# Sheet2.net
KiCad netlist of a schematic drawn in Altium Designer
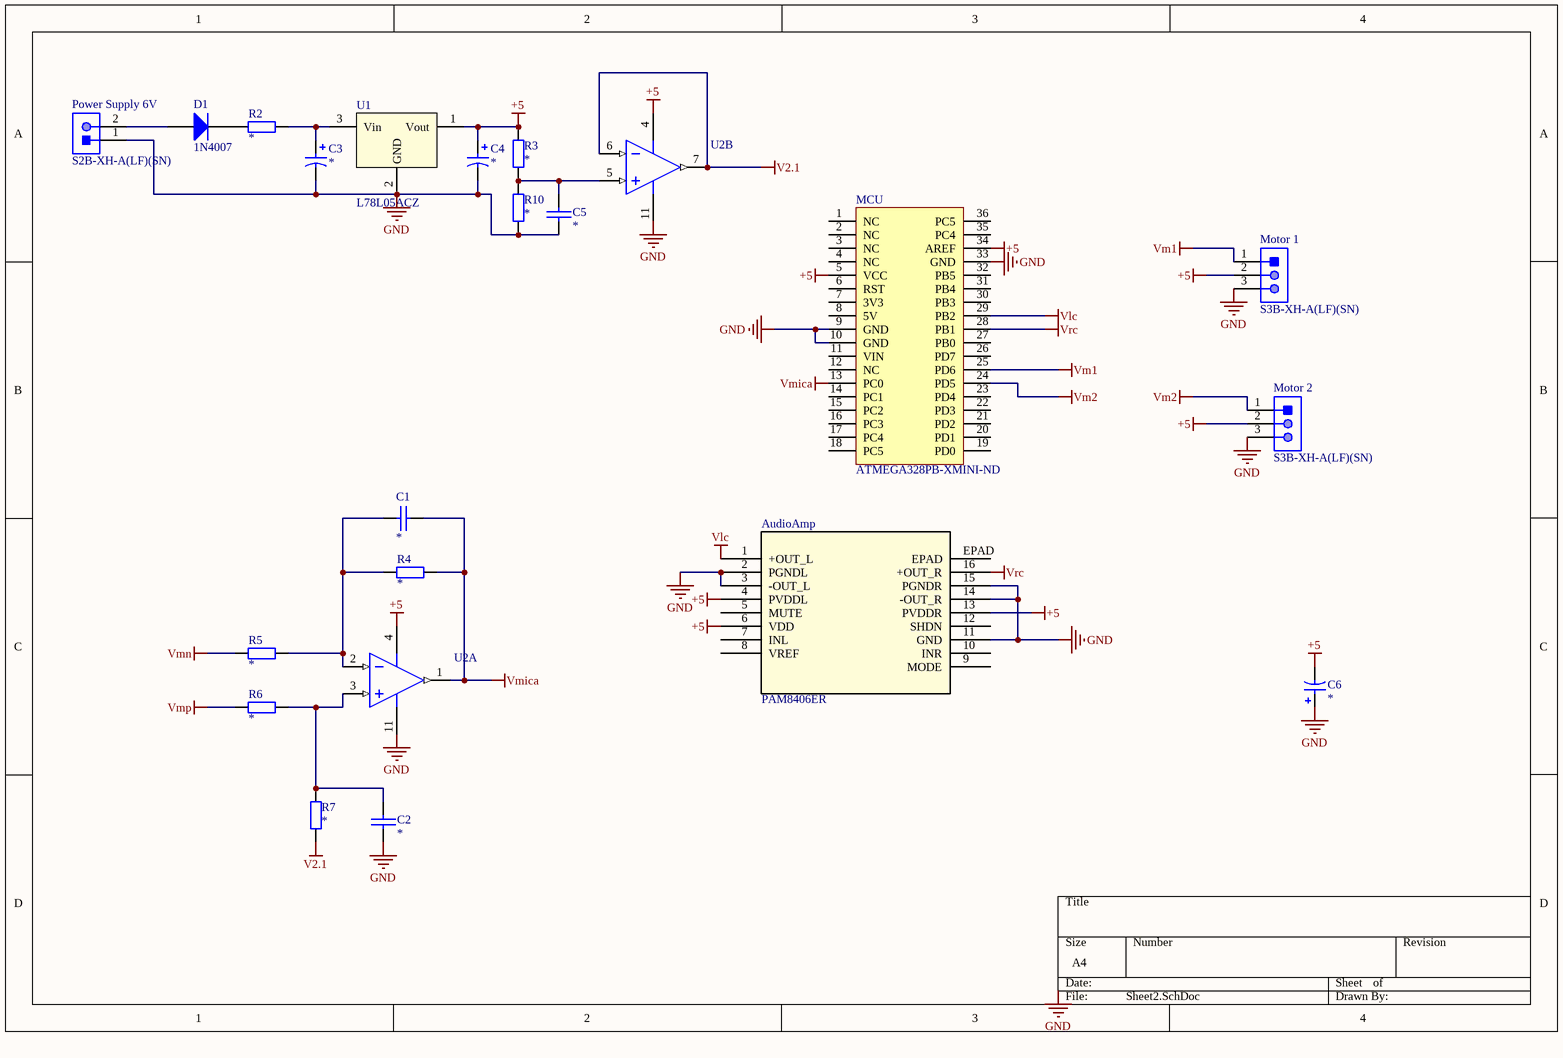
[diagram p0: Sheet2.SchDoc]

(export (version "E")
  (design (tool "Eeschema 10.0.6"))
  (components
    (comp (ref "AudioAmp")
      (value "PAM8406ER")
      (footprint "PAM8406ER_DIO")
      (description "Description")
      (fields (field (name "COPYRIGHT") "Copyright (C) 2025 Ultra Librarian. All rights reserved."))
      (libsource (lib "PAM8406ER") (part "PAM8406ER"))
    )
    (comp (ref "C1")
      (value "*")
      (footprint "CCAP-5P0")
      (description "TH ceramic capacitor with 5mm pitch")
      (libsource (lib "EE209_Library") (part "CerCap_TH_5P0"))
    )
    (comp (ref "C2")
      (value "*")
      (footprint "CCAP-5P0")
      (description "TH ceramic capacitor with 5mm pitch")
      (libsource (lib "EE209_Library") (part "CerCap_TH_5P0"))
    )
    (comp (ref "C3")
      (value "*")
      (footprint "CAP-RAD-2.5mm Pitch")
      (description "Electrolytic capacitor with radial package, 2mm pitch and 5.2mm diameter")
      (fields (field (name "PUBLISHER") "Altium Limited"))
      (libsource (lib "EE209_Library") (part "ElecCap_TH_2P0"))
    )
    (comp (ref "C4")
      (value "*")
      (footprint "CAP-RAD-2.5mm Pitch")
      (description "Electrolytic capacitor with radial package, 2mm pitch and 5.2mm diameter")
      (fields (field (name "PUBLISHER") "Altium Limited"))
      (libsource (lib "EE209_Library") (part "ElecCap_TH_2P0"))
    )
    (comp (ref "C5")
      (value "*")
      (footprint "CCAP-5P0")
      (description "TH ceramic capacitor with 5mm pitch")
      (libsource (lib "EE209_Library") (part "CerCap_TH_5P0"))
    )
    (comp (ref "C6")
      (value "*")
      (footprint "CAP-RAD-2.5mm Pitch")
      (description "Electrolytic capacitor with radial package, 2mm pitch and 5.2mm diameter")
      (fields (field (name "PUBLISHER") "Altium Limited"))
      (libsource (lib "EE209_Library") (part "ElecCap_TH_2P0"))
    )
    (comp (ref "D1")
      (value "1N4007")
      (footprint "1N4007-MFG")
      (description "1N4007 1000V standard axial diode")
      (libsource (lib "EE209_Library") (part "1N4007_TH_4AX0"))
    )
    (comp (ref "MCU")
      (value "ATmega328PB Xplained Mini Header")
      (footprint "ATmeg328P Xplained")
      (description "Dual 18-pin headers connecting to ATmega328PB Xplained Mini")
      (fields
        (field (name "MANUFACTURER") "Microchip Technology")
        (field (name "MANUFACTURER PART NUMBER") "ATMEGA328PB-XMINI")
        (field (name "SUPPLIER PART NUMBER 1") "ATMEGA328PB-XMINI-ND")
      )
      (libsource (lib "EE209_Library") (part "ATmega328PBXplained_TH"))
    )
    (comp (ref "Motor 1")
      (value "S3B-XH-A(LF)(SN)")
      (footprint "JST-S3B-XH-A(LF)(SN)_V")
      (fields (field (name "MANUFACTURER") "JST"))
      (libsource (lib "Elia Stolk") (part "CN-1P-M-R3"))
    )
    (comp (ref "Motor 2")
      (value "S3B-XH-A(LF)(SN)")
      (footprint "JST-S3B-XH-A(LF)(SN)_V")
      (fields (field (name "MANUFACTURER") "JST"))
      (libsource (lib "Elia Stolk") (part "CN-1P-M-R3"))
    )
    (comp (ref "Power Supply 6V")
      (value "S2B-XH-A(LF)(SN)")
      (footprint "JST-S2B-XH-A(LF)(SN)_V")
      (fields (field (name "MANUFACTURER") "JST"))
      (libsource (lib "Elia Stolk") (part "CN-1P-M-R2"))
    )
    (comp (ref "R2")
      (value "*")
      (footprint "AXIAL-0.4")
      (description "Through hole resistor")
      (fields (field (name "PUBLISHER") "Altium Limited"))
      (libsource (lib "EE209_Library") (part "Res_TH_0AX4"))
    )
    (comp (ref "R3")
      (value "*")
      (footprint "AXIAL-0.4")
      (description "Through hole resistor")
      (fields (field (name "PUBLISHER") "Altium Limited"))
      (libsource (lib "") (part "Res_TH_0AX4_2"))
    )
    (comp (ref "R4")
      (value "*")
      (footprint "AXIAL-0.4")
      (description "Through hole resistor")
      (fields (field (name "PUBLISHER") "Altium Limited"))
      (libsource (lib "EE209_Library") (part "Res_TH_0AX4"))
    )
    (comp (ref "R5")
      (value "*")
      (footprint "AXIAL-0.4")
      (description "Through hole resistor")
      (fields (field (name "PUBLISHER") "Altium Limited"))
      (libsource (lib "") (part "Res_TH_0AX4_1"))
    )
    (comp (ref "R6")
      (value "*")
      (footprint "AXIAL-0.4")
      (description "Through hole resistor")
      (fields (field (name "PUBLISHER") "Altium Limited"))
      (libsource (lib "") (part "Res_TH_0AX4_1"))
    )
    (comp (ref "R7")
      (value "*")
      (footprint "AXIAL-0.4")
      (description "Through hole resistor")
      (fields (field (name "PUBLISHER") "Altium Limited"))
      (libsource (lib "") (part "Res_TH_0AX4_2"))
    )
    (comp (ref "R10")
      (value "*")
      (footprint "AXIAL-0.4")
      (description "Through hole resistor")
      (fields (field (name "PUBLISHER") "Altium Limited"))
      (libsource (lib "") (part "Res_TH_0AX4_2"))
    )
    (comp (ref "U1")
      (value "L78L05ACZ")
      (footprint "TO-92")
      (description "Voltage Regulator 5V")
      (fields
        (field (name "MANUFACTURER") "ON Semiconductor")
        (field (name "MANUFACTURER PART NUMBER") "LM78L05ACZX")
      )
      (libsource (lib "EE209_Library") (part "L78L05_TH_TO92"))
    )
    (comp (ref "U2")
      (value "LM324")
      (footprint "DIP-14")
      (description "IC OPAMP GP 14DIP")
      (fields
        (field (name "MANUFACTURER") "ON Semiconductor")
        (field (name "MANUFACTURER PART NUMBER") "LM324N")
      )
      (libsource (lib "EE209_Library") (part "LM324N_TH_DIP16"))
    )
  )
  (nets
    (net (code "1") (name "+5") (class "Default")
      (node (ref "AudioAmp") (pin "13") (pinfunction "PVDDR_13") (pintype "passive"))
      (node (ref "AudioAmp") (pin "4") (pinfunction "PVDDL_4") (pintype "passive"))
      (node (ref "AudioAmp") (pin "6") (pinfunction "VDD_6") (pintype "passive"))
      (node (ref "C4") (pin "1") (pinfunction "1_1") (pintype "passive"))
      (node (ref "C6") (pin "2") (pinfunction "2_2") (pintype "passive"))
      (node (ref "MCU") (pin "34") (pinfunction "AREF_34") (pintype "passive"))
      (node (ref "MCU") (pin "5") (pinfunction "VCC_5") (pintype "power_in"))
      (node (ref "Motor 1") (pin "2") (pinfunction "2_2") (pintype "passive"))
      (node (ref "Motor 2") (pin "2") (pinfunction "2_2") (pintype "passive"))
      (node (ref "R3") (pin "2") (pinfunction "2_2") (pintype "passive"))
      (node (ref "U1") (pin "1") (pinfunction "Vout_1") (pintype "passive"))
      (node (ref "U2") (pin "4") (pinfunction "VDD_4") (pintype "power_in"))
    )
    (net (code "2") (name "GND") (class "Default")
      (node (ref "AudioAmp") (pin "11") (pinfunction "GND_11") (pintype "passive"))
      (node (ref "AudioAmp") (pin "14") (pinfunction "-OUT_R_14") (pintype "passive"))
      (node (ref "AudioAmp") (pin "15") (pinfunction "PGNDR_15") (pintype "passive"))
      (node (ref "AudioAmp") (pin "2") (pinfunction "PGNDL_2") (pintype "passive"))
      (node (ref "AudioAmp") (pin "3") (pinfunction "-OUT_L_3") (pintype "passive"))
      (node (ref "C2") (pin "1") (pinfunction "1_1") (pintype "passive"))
      (node (ref "C3") (pin "2") (pinfunction "2_2") (pintype "passive"))
      (node (ref "C4") (pin "2") (pinfunction "2_2") (pintype "passive"))
      (node (ref "C5") (pin "2") (pinfunction "2_2") (pintype "passive"))
      (node (ref "C6") (pin "1") (pinfunction "1_1") (pintype "passive"))
      (node (ref "MCU") (pin "10") (pinfunction "GND_10") (pintype "power_in"))
      (node (ref "MCU") (pin "33") (pinfunction "GND_33") (pintype "passive"))
      (node (ref "MCU") (pin "9") (pinfunction "GND_9") (pintype "power_in"))
      (node (ref "Motor 1") (pin "3") (pinfunction "3_3") (pintype "passive"))
      (node (ref "Motor 2") (pin "3") (pinfunction "3_3") (pintype "passive"))
      (node (ref "Power Supply 6V") (pin "1") (pinfunction "1_1") (pintype "passive"))
      (node (ref "R10") (pin "1") (pinfunction "1_1") (pintype "passive"))
      (node (ref "U1") (pin "2") (pinfunction "GND_2") (pintype "passive"))
      (node (ref "U2") (pin "11") (pinfunction "VSS_11") (pintype "power_in"))
    )
    (net (code "3") (name "Net-(D1-A)") (class "Default")
      (node (ref "D1") (pin "1") (pinfunction "A_1") (pintype "passive"))
      (node (ref "Power Supply 6V") (pin "2") (pinfunction "2_2") (pintype "passive"))
    )
    (net (code "4") (name "Net-(D1-K)") (class "Default")
      (node (ref "D1") (pin "2") (pinfunction "K_2") (pintype "passive"))
      (node (ref "R2") (pin "1") (pinfunction "1_1") (pintype "passive"))
    )
    (net (code "5") (name "Net-(U1-Vin)") (class "Default")
      (node (ref "C3") (pin "1") (pinfunction "1_1") (pintype "passive"))
      (node (ref "R2") (pin "2") (pinfunction "2_2") (pintype "passive"))
      (node (ref "U1") (pin "3") (pinfunction "Vin_3") (pintype "passive"))
    )
    (net (code "6") (name "Net-(U2A-VINA+)") (class "Default")
      (node (ref "C2") (pin "2") (pinfunction "2_2") (pintype "passive"))
      (node (ref "R6") (pin "1") (pinfunction "1_1") (pintype "passive"))
      (node (ref "R7") (pin "2") (pinfunction "2_2") (pintype "passive"))
      (node (ref "U2") (pin "3") (pinfunction "VINA+_3") (pintype "input"))
    )
    (net (code "7") (name "Net-(U2A-VINA-)") (class "Default")
      (node (ref "C1") (pin "1") (pinfunction "1_1") (pintype "passive"))
      (node (ref "R4") (pin "1") (pinfunction "1_1") (pintype "passive"))
      (node (ref "R5") (pin "1") (pinfunction "1_1") (pintype "passive"))
      (node (ref "U2") (pin "2") (pinfunction "VINA-_2") (pintype "input"))
    )
    (net (code "8") (name "Net-(U2B-VINB+)") (class "Default")
      (node (ref "C5") (pin "1") (pinfunction "1_1") (pintype "passive"))
      (node (ref "R10") (pin "2") (pinfunction "2_2") (pintype "passive"))
      (node (ref "R3") (pin "1") (pinfunction "1_1") (pintype "passive"))
      (node (ref "U2") (pin "5") (pinfunction "VINB+_5") (pintype "input"))
    )
    (net (code "9") (name "V2.1") (class "Default")
      (node (ref "R7") (pin "1") (pinfunction "1_1") (pintype "passive"))
      (node (ref "U2") (pin "6") (pinfunction "VINB-_6") (pintype "input"))
      (node (ref "U2") (pin "7") (pinfunction "VOUTB_7") (pintype "output"))
    )
    (net (code "10") (name "Vlc") (class "Default")
      (node (ref "AudioAmp") (pin "1") (pinfunction "+OUT_L_1") (pintype "passive"))
      (node (ref "MCU") (pin "29") (pinfunction "PB2_29") (pintype "passive"))
    )
    (net (code "11") (name "Vm1") (class "Default")
      (node (ref "MCU") (pin "25") (pinfunction "PD6_25") (pintype "passive"))
      (node (ref "Motor 1") (pin "1") (pinfunction "1_1") (pintype "passive"))
    )
    (net (code "12") (name "Vm2") (class "Default")
      (node (ref "MCU") (pin "24") (pinfunction "PD5_24") (pintype "passive"))
      (node (ref "Motor 2") (pin "1") (pinfunction "1_1") (pintype "passive"))
    )
    (net (code "13") (name "Vmica") (class "Default")
      (node (ref "C1") (pin "2") (pinfunction "2_2") (pintype "passive"))
      (node (ref "MCU") (pin "13") (pinfunction "PC0_13") (pintype "passive"))
      (node (ref "R4") (pin "2") (pinfunction "2_2") (pintype "passive"))
      (node (ref "U2") (pin "1") (pinfunction "VOUTA_1") (pintype "output"))
    )
    (net (code "14") (name "Vmn") (class "Default")
      (node (ref "R5") (pin "2") (pinfunction "2_2") (pintype "passive"))
    )
    (net (code "15") (name "Vmp") (class "Default")
      (node (ref "R6") (pin "2") (pinfunction "2_2") (pintype "passive"))
    )
    (net (code "16") (name "Vrc") (class "Default")
      (node (ref "AudioAmp") (pin "16") (pinfunction "+OUT_R_16") (pintype "passive"))
      (node (ref "MCU") (pin "28") (pinfunction "PB1_28") (pintype "passive"))
    )
    (net (code "17") (name "unconnected-(AudioAmp-INL-Pad7)") (class "Default")
      (node (ref "AudioAmp") (pin "7") (pinfunction "INL_7") (pintype "passive"))
    )
    (net (code "18") (name "unconnected-(AudioAmp-INR-Pad10)") (class "Default")
      (node (ref "AudioAmp") (pin "10") (pinfunction "INR_10") (pintype "passive"))
    )
    (net (code "19") (name "unconnected-(AudioAmp-MODE-Pad9)") (class "Default")
      (node (ref "AudioAmp") (pin "9") (pinfunction "MODE_9") (pintype "passive"))
    )
    (net (code "20") (name "unconnected-(AudioAmp-MUTE-Pad5)") (class "Default")
      (node (ref "AudioAmp") (pin "5") (pinfunction "MUTE_5") (pintype "passive"))
    )
    (net (code "21") (name "unconnected-(AudioAmp-PadEPAD)") (class "Default")
      (node (ref "AudioAmp") (pin "EPAD") (pinfunction "EPAD_EPAD") (pintype "passive"))
    )
    (net (code "22") (name "unconnected-(AudioAmp-SHDN-Pad12)") (class "Default")
      (node (ref "AudioAmp") (pin "12") (pinfunction "SHDN_12") (pintype "passive"))
    )
    (net (code "23") (name "unconnected-(AudioAmp-VREF-Pad8)") (class "Default")
      (node (ref "AudioAmp") (pin "8") (pinfunction "VREF_8") (pintype "passive"))
    )
    (net (code "24") (name "unconnected-(MCU-3V3-Pad7)") (class "Default")
      (node (ref "MCU") (pin "7") (pinfunction "3V3_7") (pintype "passive"))
    )
    (net (code "25") (name "unconnected-(MCU-5V-Pad8)") (class "Default")
      (node (ref "MCU") (pin "8") (pinfunction "5V_8") (pintype "power_in"))
    )
    (net (code "26") (name "unconnected-(MCU-NC-Pad1)") (class "Default")
      (node (ref "MCU") (pin "1") (pinfunction "NC_1") (pintype "passive"))
    )
    (net (code "27") (name "unconnected-(MCU-NC-Pad2)") (class "Default")
      (node (ref "MCU") (pin "2") (pinfunction "NC_2") (pintype "passive"))
    )
    (net (code "28") (name "unconnected-(MCU-NC-Pad3)") (class "Default")
      (node (ref "MCU") (pin "3") (pinfunction "NC_3") (pintype "passive"))
    )
    (net (code "29") (name "unconnected-(MCU-NC-Pad4)") (class "Default")
      (node (ref "MCU") (pin "4") (pinfunction "NC_4") (pintype "passive"))
    )
    (net (code "30") (name "unconnected-(MCU-NC-Pad12)") (class "Default")
      (node (ref "MCU") (pin "12") (pinfunction "NC_12") (pintype "passive"))
    )
    (net (code "31") (name "unconnected-(MCU-PB0-Pad27)") (class "Default")
      (node (ref "MCU") (pin "27") (pinfunction "PB0_27") (pintype "passive"))
    )
    (net (code "32") (name "unconnected-(MCU-PB3-Pad30)") (class "Default")
      (node (ref "MCU") (pin "30") (pinfunction "PB3_30") (pintype "passive"))
    )
    (net (code "33") (name "unconnected-(MCU-PB4-Pad31)") (class "Default")
      (node (ref "MCU") (pin "31") (pinfunction "PB4_31") (pintype "passive"))
    )
    (net (code "34") (name "unconnected-(MCU-PB5-Pad32)") (class "Default")
      (node (ref "MCU") (pin "32") (pinfunction "PB5_32") (pintype "passive"))
    )
    (net (code "35") (name "unconnected-(MCU-PC1-Pad14)") (class "Default")
      (node (ref "MCU") (pin "14") (pinfunction "PC1_14") (pintype "passive"))
    )
    (net (code "36") (name "unconnected-(MCU-PC2-Pad15)") (class "Default")
      (node (ref "MCU") (pin "15") (pinfunction "PC2_15") (pintype "passive"))
    )
    (net (code "37") (name "unconnected-(MCU-PC3-Pad16)") (class "Default")
      (node (ref "MCU") (pin "16") (pinfunction "PC3_16") (pintype "passive"))
    )
    (net (code "38") (name "unconnected-(MCU-PC4-Pad17)") (class "Default")
      (node (ref "MCU") (pin "17") (pinfunction "PC4_17") (pintype "passive"))
    )
    (net (code "39") (name "unconnected-(MCU-PC4-Pad35)") (class "Default")
      (node (ref "MCU") (pin "35") (pinfunction "PC4_35") (pintype "passive"))
    )
    (net (code "40") (name "unconnected-(MCU-PC5-Pad18)") (class "Default")
      (node (ref "MCU") (pin "18") (pinfunction "PC5_18") (pintype "passive"))
    )
    (net (code "41") (name "unconnected-(MCU-PC5-Pad36)") (class "Default")
      (node (ref "MCU") (pin "36") (pinfunction "PC5_36") (pintype "passive"))
    )
    (net (code "42") (name "unconnected-(MCU-PD0-Pad19)") (class "Default")
      (node (ref "MCU") (pin "19") (pinfunction "PD0_19") (pintype "passive"))
    )
    (net (code "43") (name "unconnected-(MCU-PD1-Pad20)") (class "Default")
      (node (ref "MCU") (pin "20") (pinfunction "PD1_20") (pintype "passive"))
    )
    (net (code "44") (name "unconnected-(MCU-PD2-Pad21)") (class "Default")
      (node (ref "MCU") (pin "21") (pinfunction "PD2_21") (pintype "passive"))
    )
    (net (code "45") (name "unconnected-(MCU-PD3-Pad22)") (class "Default")
      (node (ref "MCU") (pin "22") (pinfunction "PD3_22") (pintype "passive"))
    )
    (net (code "46") (name "unconnected-(MCU-PD4-Pad23)") (class "Default")
      (node (ref "MCU") (pin "23") (pinfunction "PD4_23") (pintype "passive"))
    )
    (net (code "47") (name "unconnected-(MCU-PD7-Pad26)") (class "Default")
      (node (ref "MCU") (pin "26") (pinfunction "PD7_26") (pintype "passive"))
    )
    (net (code "48") (name "unconnected-(MCU-RST-Pad6)") (class "Default")
      (node (ref "MCU") (pin "6") (pinfunction "RST_6") (pintype "passive"))
    )
    (net (code "49") (name "unconnected-(MCU-VIN-Pad11)") (class "Default")
      (node (ref "MCU") (pin "11") (pinfunction "VIN_11") (pintype "power_in"))
    )
  )
)
